# OCTOBOARDV_1_1.net
KiCad netlist of a schematic drawn in EAGLE
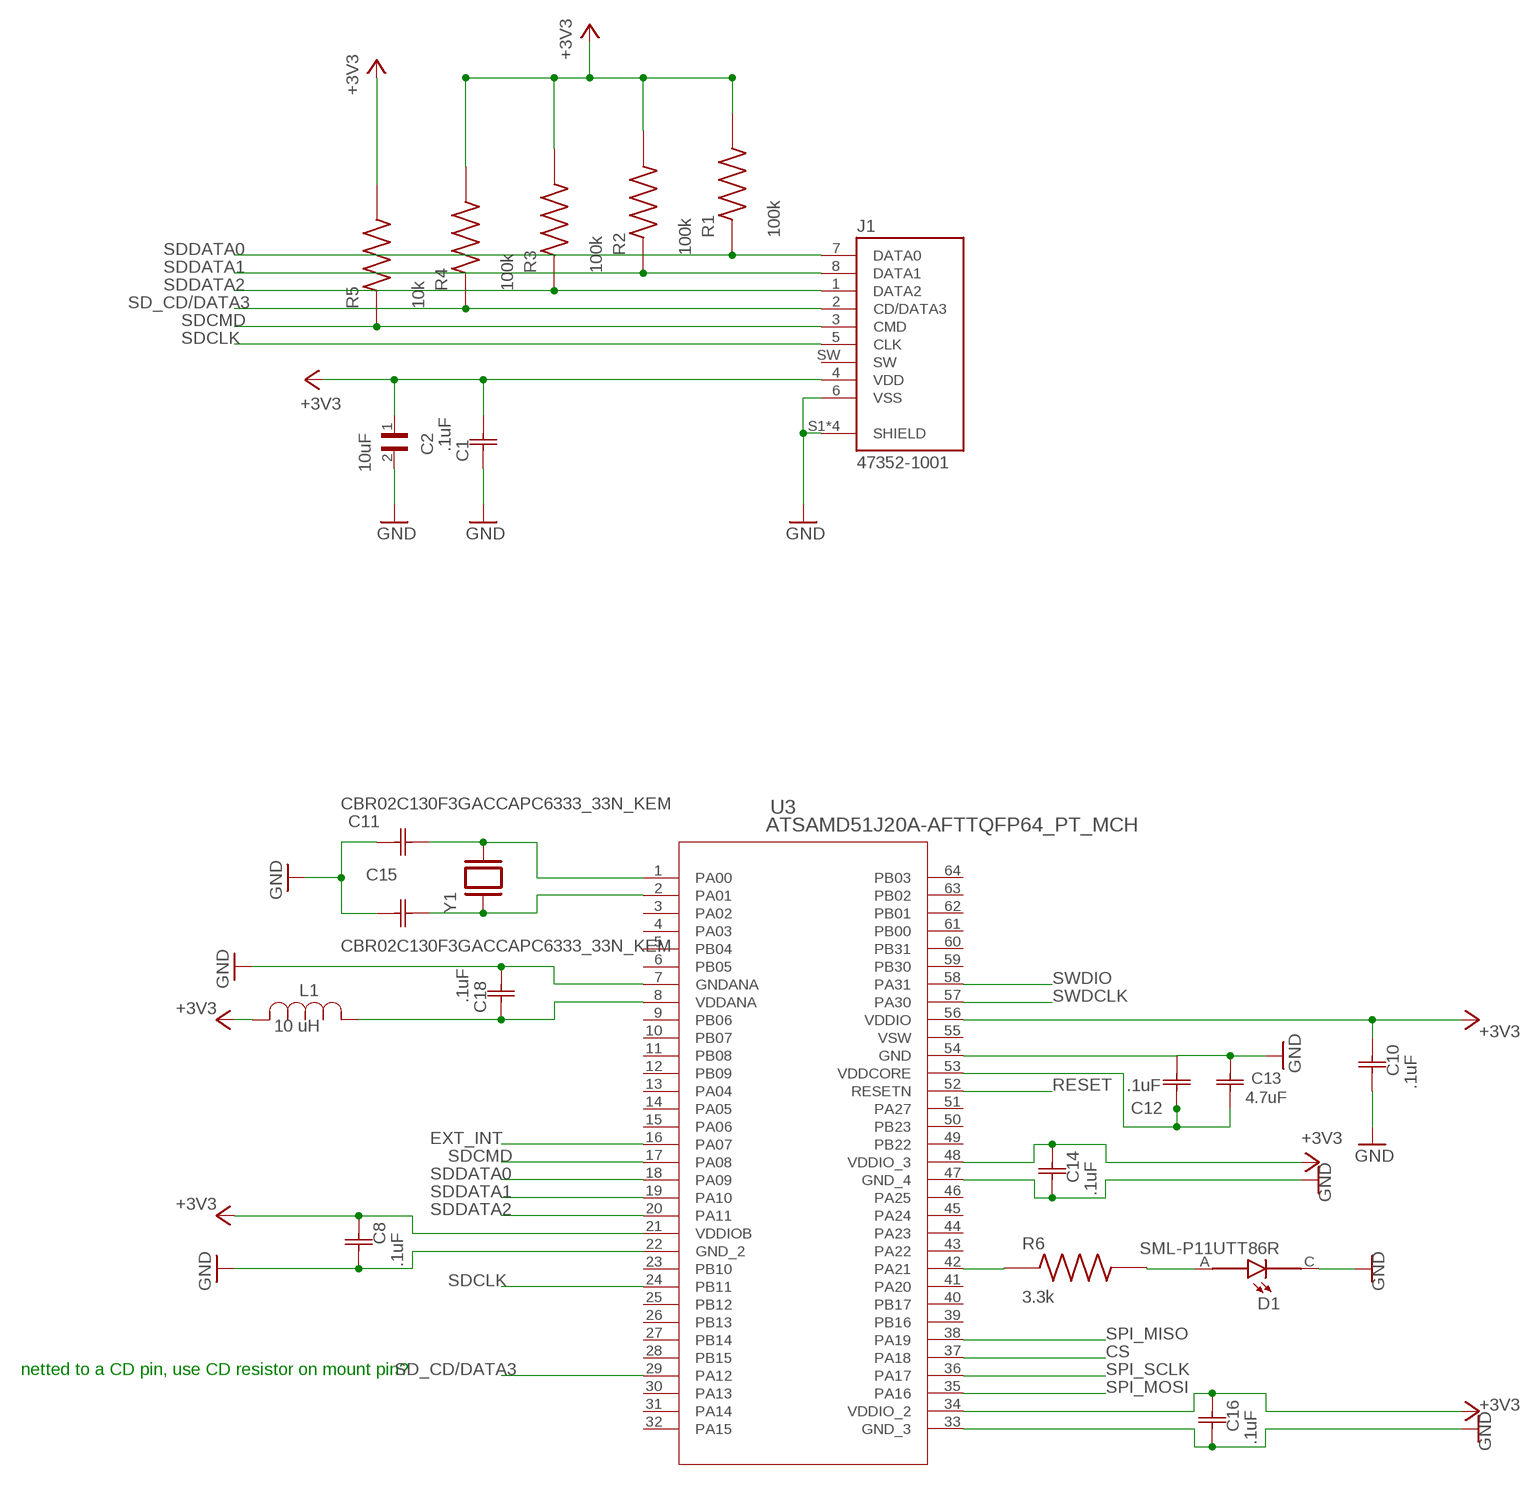
[diagram p0: schematic, sheet 1, part 1 of 2]
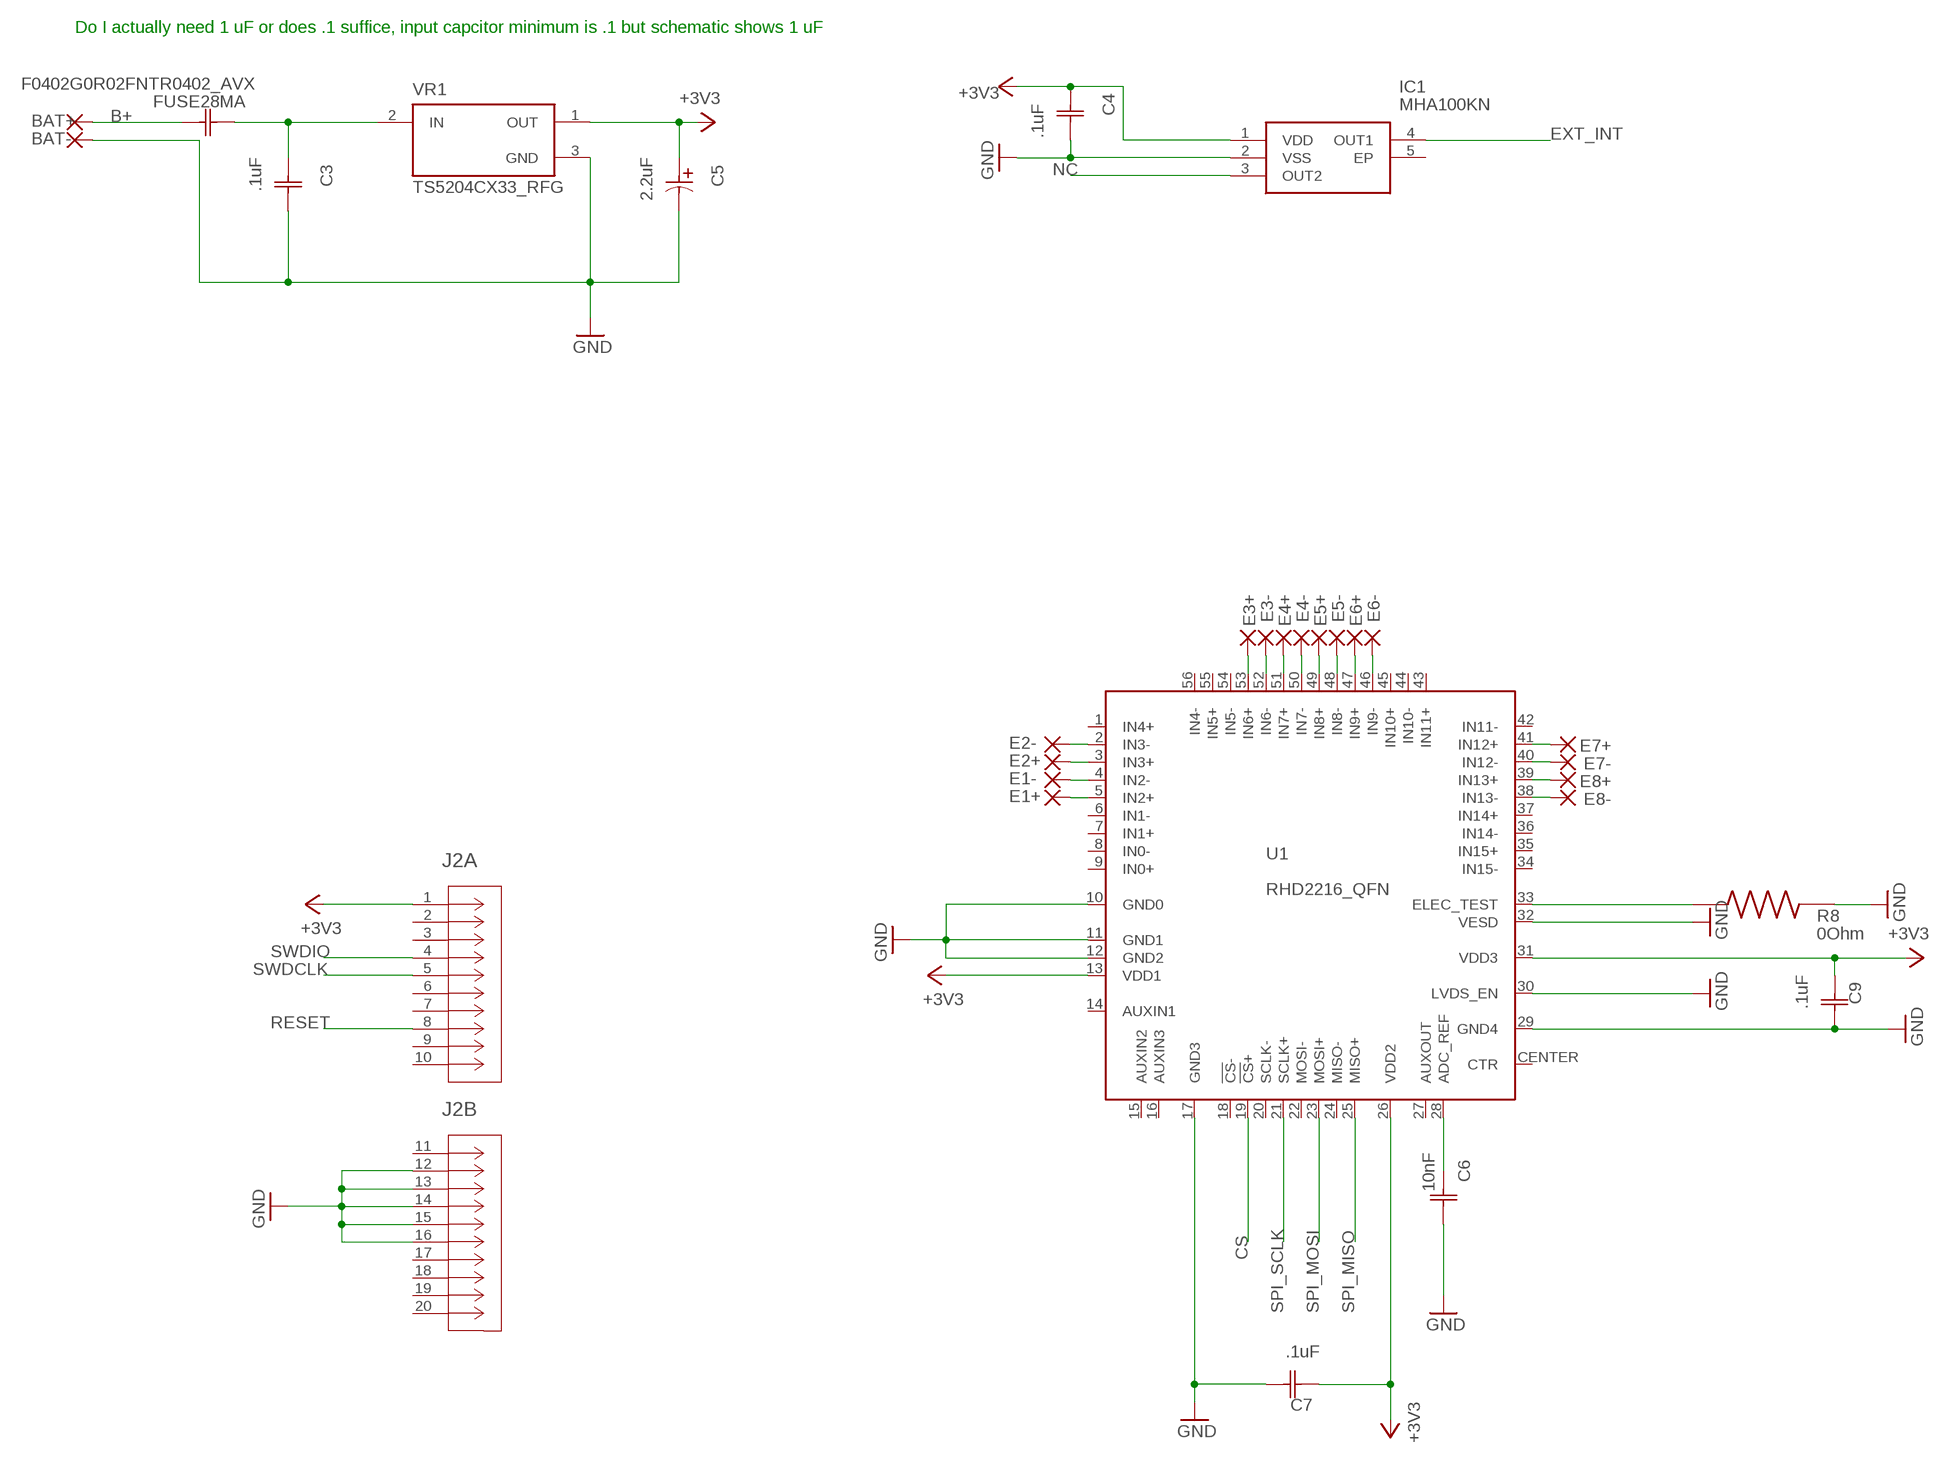
[diagram p1: schematic, sheet 1, part 2 of 2]

(export (version "E")
  (design (tool "Eeschema 10.0.6"))
  (components
    (comp (ref "BAT+")
      (value "1.36/.71LEAD")
      (footprint "eagle-import:1,6_0,9")
      (libsource (lib "eagle-import") (part "1.36/.71LEAD"))
    )
    (comp (ref "BAT-")
      (value "1.36/.71LEAD")
      (footprint "eagle-import:1,6_0,9")
      (libsource (lib "eagle-import") (part "1.36/.71LEAD"))
    )
    (comp (ref "C1")
      (value ".1uF")
      (footprint "eagle-import:CAP_0402_WAL")
      (fields
        (field (name "MANUFACTURER_PART_NUMBER") "0402B104K250CT")
        (field (name "COPYRIGHT") "Copyright (C) 2023 Ultra Librarian. All rights reserved.")
      )
      (libsource (lib "eagle-import") (part "0402B104K250CTCAP_0402_WAL"))
    )
    (comp (ref "C2")
      (value "10uF")
      (footprint "eagle-import:CAPC1005X70N")
      (fields (field (name "MF") "Murata Electronics") (field (name "MP") "GRM155R61A106ME11D"))
      (libsource (lib "eagle-import") (part "GRM155R61A106ME11D"))
    )
    (comp (ref "C3")
      (value ".1uF")
      (footprint "eagle-import:CAP_0402_WAL")
      (fields
        (field (name "MANUFACTURER_PART_NUMBER") "0402B104K250CT")
        (field (name "COPYRIGHT") "Copyright (C) 2023 Ultra Librarian. All rights reserved.")
      )
      (libsource (lib "eagle-import") (part "0402B104K250CTCAP_0402_WAL"))
    )
    (comp (ref "C4")
      (value ".1uF")
      (footprint "eagle-import:CAP_0402_WAL")
      (fields
        (field (name "MANUFACTURER_PART_NUMBER") "0402B104K250CT")
        (field (name "COPYRIGHT") "Copyright (C) 2023 Ultra Librarian. All rights reserved.")
      )
      (libsource (lib "eagle-import") (part "0402B104K250CTCAP_0402_WAL"))
    )
    (comp (ref "C5")
      (value "2.2uF")
      (footprint "eagle-import:CAPMP3.4X1.6_1.8N_KEM")
      (fields
        (field (name "MANUFACTURER_PART_NUMBER") "T491A225K016ATAUTO")
        (field (name "COPYRIGHT") "Copyright (C) 2023 Ultra Librarian. All rights reserved.")
      )
      (libsource (lib "eagle-import") (part "T491A225K016ATAUTOCAPMP3.4X1.6_1.8N_KEM"))
    )
    (comp (ref "C6")
      (value "10nF")
      (footprint "eagle-import:CAP_00J25AH_AVX")
      (fields
        (field (name "MANUFACTURER_PART_NUMBER") "CM02X5R103M16AH")
        (field (name "COPYRIGHT") "Copyright (C) 2023 Ultra Librarian. All rights reserved.")
      )
      (libsource (lib "eagle-import") (part "CM02X5R103M16AHCAP_00J25AH_AVX"))
    )
    (comp (ref "C7")
      (value ".1uF")
      (footprint "eagle-import:CAP_0402_WAL")
      (fields
        (field (name "MANUFACTURER_PART_NUMBER") "0402B104K250CT")
        (field (name "COPYRIGHT") "Copyright (C) 2023 Ultra Librarian. All rights reserved.")
      )
      (libsource (lib "eagle-import") (part "0402B104K250CTCAP_0402_WAL"))
    )
    (comp (ref "C8")
      (value ".1uF")
      (footprint "eagle-import:CAP_0402_WAL")
      (fields
        (field (name "MANUFACTURER_PART_NUMBER") "0402B104K250CT")
        (field (name "COPYRIGHT") "Copyright (C) 2023 Ultra Librarian. All rights reserved.")
      )
      (libsource (lib "eagle-import") (part "0402B104K250CTCAP_0402_WAL"))
    )
    (comp (ref "C9")
      (value ".1uF")
      (footprint "eagle-import:CAP_0402_WAL")
      (fields
        (field (name "MANUFACTURER_PART_NUMBER") "0402B104K250CT")
        (field (name "COPYRIGHT") "Copyright (C) 2023 Ultra Librarian. All rights reserved.")
      )
      (libsource (lib "eagle-import") (part "0402B104K250CTCAP_0402_WAL"))
    )
    (comp (ref "C10")
      (value ".1uF")
      (footprint "eagle-import:CAP_0402_WAL")
      (fields
        (field (name "MANUFACTURER_PART_NUMBER") "0402B104K250CT")
        (field (name "COPYRIGHT") "Copyright (C) 2023 Ultra Librarian. All rights reserved.")
      )
      (libsource (lib "eagle-import") (part "0402B104K250CTCAP_0402_WAL"))
    )
    (comp (ref "C11")
      (value "CBR02C130F3GACCAPC6333_33N_KEM")
      (footprint "eagle-import:CAPC6333_33N_KEM")
      (fields
        (field (name "MANUFACTURER_PART_NUMBER") "CBR02C130F3GAC")
        (field (name "COPYRIGHT") "Copyright (C) 2023 Ultra Librarian. All rights reserved.")
      )
      (libsource (lib "eagle-import") (part "CBR02C130F3GACCAPC6333_33N_KEM"))
    )
    (comp (ref "C12")
      (value ".1uF")
      (footprint "eagle-import:CAP_0402_WAL")
      (fields
        (field (name "MANUFACTURER_PART_NUMBER") "0402B104K250CT")
        (field (name "COPYRIGHT") "Copyright (C) 2023 Ultra Librarian. All rights reserved.")
      )
      (libsource (lib "eagle-import") (part "0402B104K250CTCAP_0402_WAL"))
    )
    (comp (ref "C13")
      (value "4.7uF")
      (footprint "eagle-import:CAP_CM03_F_KAV")
      (fields
        (field (name "MANUFACTURER_PART_NUMBER") "CM03X5R475M06AH055")
        (field (name "COPYRIGHT") "Copyright (C) 2023 Ultra Librarian. All rights reserved.")
      )
      (libsource (lib "eagle-import") (part "CM03X5R475M06AH055CAP_CM03_F_KAV"))
    )
    (comp (ref "C14")
      (value ".1uF")
      (footprint "eagle-import:CAP_0402_WAL")
      (fields
        (field (name "MANUFACTURER_PART_NUMBER") "0402B104K250CT")
        (field (name "COPYRIGHT") "Copyright (C) 2023 Ultra Librarian. All rights reserved.")
      )
      (libsource (lib "eagle-import") (part "0402B104K250CTCAP_0402_WAL"))
    )
    (comp (ref "C15")
      (value "CBR02C130F3GACCAPC6333_33N_KEM")
      (footprint "eagle-import:CAPC6333_33N_KEM")
      (fields
        (field (name "MANUFACTURER_PART_NUMBER") "CBR02C130F3GAC")
        (field (name "COPYRIGHT") "Copyright (C) 2023 Ultra Librarian. All rights reserved.")
      )
      (libsource (lib "eagle-import") (part "CBR02C130F3GACCAPC6333_33N_KEM"))
    )
    (comp (ref "C16")
      (value ".1uF")
      (footprint "eagle-import:CAP_0402_WAL")
      (fields
        (field (name "MANUFACTURER_PART_NUMBER") "0402B104K250CT")
        (field (name "COPYRIGHT") "Copyright (C) 2023 Ultra Librarian. All rights reserved.")
      )
      (libsource (lib "eagle-import") (part "0402B104K250CTCAP_0402_WAL"))
    )
    (comp (ref "C18")
      (value ".1uF")
      (footprint "eagle-import:CAP_0402_WAL")
      (fields
        (field (name "MANUFACTURER_PART_NUMBER") "0402B104K250CT")
        (field (name "COPYRIGHT") "Copyright (C) 2023 Ultra Librarian. All rights reserved.")
      )
      (libsource (lib "eagle-import") (part "0402B104K250CTCAP_0402_WAL"))
    )
    (comp (ref "D1")
      (value "SML-P11UTT86R")
      (footprint "eagle-import:LED_SML-P11UTT86R")
      (fields (field (name "MANUFACTURER") "ROHM Semiconductor"))
      (libsource (lib "eagle-import") (part "SML-P11UTT86R"))
    )
    (comp (ref "E1+")
      (value "1.36/.71LEAD")
      (footprint "eagle-import:1,6_0,9")
      (libsource (lib "eagle-import") (part "1.36/.71LEAD"))
    )
    (comp (ref "E1-")
      (value "1.36/.71LEAD")
      (footprint "eagle-import:1,6_0,9")
      (libsource (lib "eagle-import") (part "1.36/.71LEAD"))
    )
    (comp (ref "E2+")
      (value "1.36/.71LEAD")
      (footprint "eagle-import:1,6_0,9")
      (libsource (lib "eagle-import") (part "1.36/.71LEAD"))
    )
    (comp (ref "E2-")
      (value "1.36/.71LEAD")
      (footprint "eagle-import:1,6_0,9")
      (libsource (lib "eagle-import") (part "1.36/.71LEAD"))
    )
    (comp (ref "E3+")
      (value "1.36/.71LEAD")
      (footprint "eagle-import:1,6_0,9")
      (libsource (lib "eagle-import") (part "1.36/.71LEAD"))
    )
    (comp (ref "E3-")
      (value "1.36/.71LEAD")
      (footprint "eagle-import:1,6_0,9")
      (libsource (lib "eagle-import") (part "1.36/.71LEAD"))
    )
    (comp (ref "E4+")
      (value "1.36/.71LEAD")
      (footprint "eagle-import:1,6_0,9")
      (libsource (lib "eagle-import") (part "1.36/.71LEAD"))
    )
    (comp (ref "E4-")
      (value "1.36/.71LEAD")
      (footprint "eagle-import:1,6_0,9")
      (libsource (lib "eagle-import") (part "1.36/.71LEAD"))
    )
    (comp (ref "E5+")
      (value "1.36/.71LEAD")
      (footprint "eagle-import:1,6_0,9")
      (libsource (lib "eagle-import") (part "1.36/.71LEAD"))
    )
    (comp (ref "E5-")
      (value "1.36/.71LEAD")
      (footprint "eagle-import:1,6_0,9")
      (libsource (lib "eagle-import") (part "1.36/.71LEAD"))
    )
    (comp (ref "E6+")
      (value "1.36/.71LEAD")
      (footprint "eagle-import:1,6_0,9")
      (libsource (lib "eagle-import") (part "1.36/.71LEAD"))
    )
    (comp (ref "E6-")
      (value "1.36/.71LEAD")
      (footprint "eagle-import:1,6_0,9")
      (libsource (lib "eagle-import") (part "1.36/.71LEAD"))
    )
    (comp (ref "E7+")
      (value "1.36/.71LEAD")
      (footprint "eagle-import:1,6_0,9")
      (libsource (lib "eagle-import") (part "1.36/.71LEAD"))
    )
    (comp (ref "E7-")
      (value "1.36/.71LEAD")
      (footprint "eagle-import:1,6_0,9")
      (libsource (lib "eagle-import") (part "1.36/.71LEAD"))
    )
    (comp (ref "E8+")
      (value "1.36/.71LEAD")
      (footprint "eagle-import:1,6_0,9")
      (libsource (lib "eagle-import") (part "1.36/.71LEAD"))
    )
    (comp (ref "E8-")
      (value "1.36/.71LEAD")
      (footprint "eagle-import:1,6_0,9")
      (libsource (lib "eagle-import") (part "1.36/.71LEAD"))
    )
    (comp (ref "FUSE28MA")
      (value "F0402G0R02FNTR0402_AVX")
      (footprint "eagle-import:0402_AVX")
      (fields
        (field (name "MANUFACTURER_PART_NUMBER") "F0402G0R20FNTR")
        (field (name "COPYRIGHT") "Copyright (C) 2023 Ultra Librarian. All rights reserved.")
      )
      (libsource (lib "eagle-import") (part "F0402G0R20FNTR0402_AVX"))
    )
    (comp (ref "IC1")
      (value "MHA100KN")
      (footprint "eagle-import:MHA100KN")
      (fields (field (name "MOUSER_PART_NUMBER") "438-MHA100KN"))
      (libsource (lib "eagle-import") (part "MHA100KN"))
    )
    (comp (ref "J1")
      (value "47352-1001")
      (footprint "eagle-import:MOLEX_47352-1001")
      (fields (field (name "DIGI-KEY_PART_NUMBER") "WM3290CT-ND") (field (name "MF") "Molex"))
      (libsource (lib "eagle-import") (part "47352-1001"))
    )
    (comp (ref "J2")
      (value "PRPC040DAAN-RCCONN80_PRP-040_4000X197_SUL")
      (footprint "eagle-import:CONN80_PRP-040_4000X197_SUL")
      (fields
        (field (name "MANUFACTURER_PART_NUMBER") "PRPC040DAAN-RC")
        (field (name "COPYRIGHT") "Copyright (C) 2023 Ultra Librarian. All rights reserved.")
      )
      (libsource (lib "eagle-import") (part "PRPC040DAAN-RCCONN80_PRP-040_4000X197_SUL"))
    )
    (comp (ref "L1")
      (value "10 uH")
      (footprint "eagle-import:IND_SDEB12101T_CYN")
      (fields
        (field (name "MANUFACTURER_PART_NUMBER") "SDEB12101T-100MSD")
        (field (name "COPYRIGHT") "Copyright (C) 2023 Ultra Librarian. All rights reserved.")
      )
      (libsource (lib "eagle-import") (part "SDEB12101T-100MSDIND_SDEB12101T_CYN"))
    )
    (comp (ref "R1")
      (value "100k")
      (footprint "eagle-import:RES_ERJ1GNJ104C")
      (fields (field (name "MF") "Panasonic") (field (name "MP") "ERJ-1GNJ104C"))
      (libsource (lib "eagle-import") (part "ERJ1GNJ104C"))
    )
    (comp (ref "R2")
      (value "100k")
      (footprint "eagle-import:RES_ERJ1GNJ104C")
      (fields (field (name "MF") "Panasonic") (field (name "MP") "ERJ-1GNJ104C"))
      (libsource (lib "eagle-import") (part "ERJ1GNJ104C"))
    )
    (comp (ref "R3")
      (value "100k")
      (footprint "eagle-import:RES_ERJ1GNJ104C")
      (fields (field (name "MF") "Panasonic") (field (name "MP") "ERJ-1GNJ104C"))
      (libsource (lib "eagle-import") (part "ERJ1GNJ104C"))
    )
    (comp (ref "R4")
      (value "100k")
      (footprint "eagle-import:RES_ERJ1GNJ104C")
      (fields (field (name "MF") "Panasonic") (field (name "MP") "ERJ-1GNJ104C"))
      (libsource (lib "eagle-import") (part "ERJ1GNJ104C"))
    )
    (comp (ref "R5")
      (value "10k")
      (footprint "eagle-import:RES_ERJ-1RHD1002C")
      (fields (field (name "MF") "Panasonic Electronic") (field (name "MP") "ERJ-1RHD1002C"))
      (libsource (lib "eagle-import") (part "ERJ-1RHD1002C"))
    )
    (comp (ref "R6")
      (value "3.3k")
      (footprint "eagle-import:RESC0603X26N")
      (libsource (lib "eagle-import") (part "ERJ-1GNF3301C"))
    )
    (comp (ref "R8")
      (value "0Ohm")
      (footprint "eagle-import:RESC0603X26N")
      (fields (field (name "MF") "Stackpole Electronics Inc") (field (name "MP") "RMCF0201ZT0R00"))
      (libsource (lib "eagle-import") (part "RMCF0201ZT0R00"))
    )
    (comp (ref "U1")
      (value "RHD2216_QFN")
      (footprint "eagle-import:QFN56_8_X_8_LARGE")
      (libsource (lib "eagle-import") (part "RHD2216_QFN"))
    )
    (comp (ref "U3")
      (value "ATSAMD51J20A-AFTTQFP64_PT_MCH")
      (footprint "eagle-import:TQFP64_PT_MCH")
      (fields
        (field (name "MANUFACTURER_PART_NUMBER") "ATSAMD51J20A-AFT")
        (field (name "COPYRIGHT") "Copyright (C) 2023 Ultra Librarian. All rights reserved.")
      )
      (libsource (lib "eagle-import") (part "ATSAMD51J20A-AFTTQFP64_PT_MCH"))
    )
    (comp (ref "VR1")
      (value "TS5204CX33_RFG")
      (footprint "eagle-import:SOT95P280X110-3N")
      (fields (field (name "MF") "Taiwan Semiconductor Corporation") (field (name "MP") "TS5204CX33 RFG"))
      (libsource (lib "eagle-import") (part "TS5204CX33_RFG"))
    )
    (comp (ref "Y1")
      (value "CM9V-T1A-32.768KHZ-9PF-20PPM-TA-QC")
      (footprint "eagle-import:XTAL_CM9V-T1A-32.768KHZ-9PF-20PPM-TA-QC")
      (fields (field (name "MF") "Micro Crystal AG"))
      (libsource (lib "eagle-import") (part "CM9V-T1A-32.768KHZ-9PF-20PPM-TA-QC"))
    )
  )
  (nets
    (net (code "1") (name "+3V3") (class "Default")
      (node (ref "C1") (pin "2") (pinfunction "2_2") (pintype "passive"))
      (node (ref "C10") (pin "1") (pinfunction "1_1") (pintype "passive"))
      (node (ref "C14") (pin "1") (pinfunction "1_1") (pintype "passive"))
      (node (ref "C16") (pin "1") (pinfunction "1_1") (pintype "passive"))
      (node (ref "C2") (pin "1") (pinfunction "1_1") (pintype "passive"))
      (node (ref "C4") (pin "1") (pinfunction "1_1") (pintype "passive"))
      (node (ref "C5") (pin "1") (pinfunction "1_1") (pintype "passive"))
      (node (ref "C7") (pin "1") (pinfunction "1_1") (pintype "passive"))
      (node (ref "C8") (pin "1") (pinfunction "1_1") (pintype "passive"))
      (node (ref "C9") (pin "1") (pinfunction "1_1") (pintype "passive"))
      (node (ref "IC1") (pin "1") (pinfunction "VDD_1") (pintype "bidirectional"))
      (node (ref "J1") (pin "4") (pinfunction "VDD_4") (pintype "passive"))
      (node (ref "J2") (pin "1") (pinfunction "1_1") (pintype "passive"))
      (node (ref "L1") (pin "2") (pinfunction "2_2") (pintype "passive"))
      (node (ref "R1") (pin "2") (pinfunction "2_2") (pintype "passive"))
      (node (ref "R2") (pin "2") (pinfunction "2_2") (pintype "passive"))
      (node (ref "R3") (pin "2") (pinfunction "2_2") (pintype "passive"))
      (node (ref "R4") (pin "2") (pinfunction "2_2") (pintype "passive"))
      (node (ref "R5") (pin "2") (pinfunction "2_2") (pintype "passive"))
      (node (ref "U1") (pin "13") (pinfunction "VDD1_13") (pintype "power_in"))
      (node (ref "U1") (pin "26") (pinfunction "VDD2_26") (pintype "power_in"))
      (node (ref "U1") (pin "31") (pinfunction "VDD3_31") (pintype "power_in"))
      (node (ref "U3") (pin "21") (pinfunction "VDDIOB_21") (pintype "power_in"))
      (node (ref "U3") (pin "34") (pinfunction "VDDIO_2_34") (pintype "power_in"))
      (node (ref "U3") (pin "48") (pinfunction "VDDIO_3_48") (pintype "power_in"))
      (node (ref "U3") (pin "56") (pinfunction "VDDIO_56") (pintype "power_in"))
      (node (ref "VR1") (pin "1") (pinfunction "OUT_1") (pintype "output"))
    )
    (net (code "2") (name "/B+") (class "Default")
      (node (ref "BAT+") (pin "1") (pinfunction "P_1") (pintype "passive"))
      (node (ref "FUSE28MA") (pin "1") (pinfunction "11_1") (pintype "passive"))
    )
    (net (code "3") (name "/CS") (class "Default")
      (node (ref "U1") (pin "19") (pinfunction "~{CS}+_19") (pintype "input"))
      (node (ref "U3") (pin "37") (pinfunction "PA18_37") (pintype "bidirectional"))
    )
    (net (code "4") (name "/CTR") (class "Default")
      (node (ref "U1") (pin "CENTER") (pinfunction "CTR_CENTER") (pintype "power_in"))
    )
    (net (code "5") (name "/EXT_INT") (class "Default")
      (node (ref "IC1") (pin "4") (pinfunction "OUT1_4") (pintype "bidirectional"))
      (node (ref "U3") (pin "16") (pinfunction "PA07_16") (pintype "bidirectional"))
    )
    (net (code "6") (name "/NC") (class "Default")
      (node (ref "IC1") (pin "3") (pinfunction "OUT2_3") (pintype "bidirectional"))
    )
    (net (code "7") (name "/RESET") (class "Default")
      (node (ref "J2") (pin "8") (pinfunction "8_8") (pintype "passive"))
      (node (ref "U3") (pin "52") (pinfunction "RESETN_52") (pintype "input"))
    )
    (net (code "8") (name "/SDCLK") (class "Default")
      (node (ref "J1") (pin "5") (pinfunction "CLK_5") (pintype "passive"))
      (node (ref "U3") (pin "24") (pinfunction "PB11_24") (pintype "bidirectional"))
    )
    (net (code "9") (name "/SDCMD") (class "Default")
      (node (ref "J1") (pin "3") (pinfunction "CMD_3") (pintype "passive"))
      (node (ref "R5") (pin "1") (pinfunction "1_1") (pintype "passive"))
      (node (ref "U3") (pin "17") (pinfunction "PA08_17") (pintype "bidirectional"))
    )
    (net (code "10") (name "/SDDATA0") (class "Default")
      (node (ref "J1") (pin "7") (pinfunction "DATA0_7") (pintype "passive"))
      (node (ref "R1") (pin "1") (pinfunction "1_1") (pintype "passive"))
      (node (ref "U3") (pin "18") (pinfunction "PA09_18") (pintype "bidirectional"))
    )
    (net (code "11") (name "/SDDATA1") (class "Default")
      (node (ref "J1") (pin "8") (pinfunction "DATA1_8") (pintype "passive"))
      (node (ref "R2") (pin "1") (pinfunction "1_1") (pintype "passive"))
      (node (ref "U3") (pin "19") (pinfunction "PA10_19") (pintype "bidirectional"))
    )
    (net (code "12") (name "/SDDATA2") (class "Default")
      (node (ref "J1") (pin "1") (pinfunction "DATA2_1") (pintype "passive"))
      (node (ref "R3") (pin "1") (pinfunction "1_1") (pintype "passive"))
      (node (ref "U3") (pin "20") (pinfunction "PA11_20") (pintype "bidirectional"))
    )
    (net (code "13") (name "/SD_CD{slash}DATA3") (class "Default")
      (node (ref "J1") (pin "2") (pinfunction "CD/DATA3_2") (pintype "passive"))
      (node (ref "R4") (pin "1") (pinfunction "1_1") (pintype "passive"))
      (node (ref "U3") (pin "29") (pinfunction "PA12_29") (pintype "bidirectional"))
    )
    (net (code "14") (name "/SPI_MISO") (class "Default")
      (node (ref "U1") (pin "25") (pinfunction "MISO+_25") (pintype "output"))
      (node (ref "U3") (pin "38") (pinfunction "PA19_38") (pintype "bidirectional"))
    )
    (net (code "15") (name "/SPI_MOSI") (class "Default")
      (node (ref "U1") (pin "23") (pinfunction "MOSI+_23") (pintype "input"))
      (node (ref "U3") (pin "35") (pinfunction "PA16_35") (pintype "bidirectional"))
    )
    (net (code "16") (name "/SPI_SCLK") (class "Default")
      (node (ref "U1") (pin "21") (pinfunction "SCLK+_21") (pintype "input"))
      (node (ref "U3") (pin "36") (pinfunction "PA17_36") (pintype "bidirectional"))
    )
    (net (code "17") (name "/SWDCLK") (class "Default")
      (node (ref "J2") (pin "5") (pinfunction "5_5") (pintype "passive"))
      (node (ref "U3") (pin "57") (pinfunction "PA30_57") (pintype "bidirectional"))
    )
    (net (code "18") (name "/SWDIO") (class "Default")
      (node (ref "J2") (pin "4") (pinfunction "4_4") (pintype "passive"))
      (node (ref "U3") (pin "58") (pinfunction "PA31_58") (pintype "bidirectional"))
    )
    (net (code "19") (name "/VSW") (class "Default")
      (node (ref "U3") (pin "55") (pinfunction "VSW_55") (pintype "power_in"))
    )
    (net (code "20") (name "GND") (class "Default")
      (node (ref "BAT-") (pin "1") (pinfunction "P_1") (pintype "passive"))
      (node (ref "C1") (pin "1") (pinfunction "1_1") (pintype "passive"))
      (node (ref "C10") (pin "2") (pinfunction "2_2") (pintype "passive"))
      (node (ref "C11") (pin "1") (pinfunction "1_1") (pintype "passive"))
      (node (ref "C12") (pin "2") (pinfunction "2_2") (pintype "passive"))
      (node (ref "C13") (pin "2") (pinfunction "2_2") (pintype "passive"))
      (node (ref "C14") (pin "2") (pinfunction "2_2") (pintype "passive"))
      (node (ref "C15") (pin "1") (pinfunction "1_1") (pintype "passive"))
      (node (ref "C16") (pin "2") (pinfunction "2_2") (pintype "passive"))
      (node (ref "C18") (pin "2") (pinfunction "2_2") (pintype "passive"))
      (node (ref "C2") (pin "2") (pinfunction "2_2") (pintype "passive"))
      (node (ref "C3") (pin "2") (pinfunction "2_2") (pintype "passive"))
      (node (ref "C4") (pin "2") (pinfunction "2_2") (pintype "passive"))
      (node (ref "C5") (pin "2") (pinfunction "2_2") (pintype "passive"))
      (node (ref "C6") (pin "2") (pinfunction "2_2") (pintype "passive"))
      (node (ref "C7") (pin "2") (pinfunction "2_2") (pintype "passive"))
      (node (ref "C8") (pin "2") (pinfunction "2_2") (pintype "passive"))
      (node (ref "C9") (pin "2") (pinfunction "2_2") (pintype "passive"))
      (node (ref "D1") (pin "C") (pinfunction "C_C") (pintype "passive"))
      (node (ref "IC1") (pin "2") (pinfunction "VSS_2") (pintype "bidirectional"))
      (node (ref "J1") (pin "6") (pinfunction "VSS_6") (pintype "passive"))
      (node (ref "J1") (pin "S1") (pinfunction "SHIELD_S1") (pintype "passive"))
      (node (ref "J1") (pin "S2") (pinfunction "SHIELD_S2") (pintype "passive"))
      (node (ref "J1") (pin "S3") (pinfunction "SHIELD_S3") (pintype "passive"))
      (node (ref "J1") (pin "S4") (pinfunction "SHIELD_S4") (pintype "passive"))
      (node (ref "J2") (pin "12") (pinfunction "42_12") (pintype "passive"))
      (node (ref "J2") (pin "13") (pinfunction "43_13") (pintype "passive"))
      (node (ref "J2") (pin "14") (pinfunction "44_14") (pintype "passive"))
      (node (ref "J2") (pin "15") (pinfunction "45_15") (pintype "passive"))
      (node (ref "J2") (pin "16") (pinfunction "46_16") (pintype "passive"))
      (node (ref "R8") (pin "2") (pinfunction "2_2") (pintype "passive"))
      (node (ref "U1") (pin "10") (pinfunction "GND0_10") (pintype "input"))
      (node (ref "U1") (pin "11") (pinfunction "GND1_11") (pintype "power_in"))
      (node (ref "U1") (pin "12") (pinfunction "GND2_12") (pintype "power_in"))
      (node (ref "U1") (pin "17") (pinfunction "GND3_17") (pintype "power_in"))
      (node (ref "U1") (pin "29") (pinfunction "GND4_29") (pintype "power_in"))
      (node (ref "U1") (pin "30") (pinfunction "LVDS_EN_30") (pintype "input"))
      (node (ref "U1") (pin "32") (pinfunction "VESD_32") (pintype "power_in"))
      (node (ref "U3") (pin "22") (pinfunction "GND_2_22") (pintype "passive"))
      (node (ref "U3") (pin "33") (pinfunction "GND_3_33") (pintype "passive"))
      (node (ref "U3") (pin "47") (pinfunction "GND_4_47") (pintype "passive"))
      (node (ref "U3") (pin "54") (pinfunction "GND_54") (pintype "passive"))
      (node (ref "U3") (pin "7") (pinfunction "GNDANA_7") (pintype "passive"))
      (node (ref "VR1") (pin "3") (pinfunction "GND_3") (pintype "power_in"))
    )
    (net (code "21") (name "Net-(D1-PadA)") (class "Default")
      (node (ref "D1") (pin "A") (pinfunction "A_A") (pintype "passive"))
      (node (ref "R6") (pin "2") (pinfunction "2_2") (pintype "passive"))
    )
    (net (code "22") (name "Net-(E1+-P)") (class "Default")
      (node (ref "E1+") (pin "1") (pinfunction "P_1") (pintype "passive"))
      (node (ref "U1") (pin "5") (pinfunction "IN2+_5") (pintype "input"))
    )
    (net (code "23") (name "Net-(E1--P)") (class "Default")
      (node (ref "E1-") (pin "1") (pinfunction "P_1") (pintype "passive"))
      (node (ref "U1") (pin "4") (pinfunction "IN2-_4") (pintype "input"))
    )
    (net (code "24") (name "Net-(E2+-P)") (class "Default")
      (node (ref "E2+") (pin "1") (pinfunction "P_1") (pintype "passive"))
      (node (ref "U1") (pin "3") (pinfunction "IN3+_3") (pintype "input"))
    )
    (net (code "25") (name "Net-(E2--P)") (class "Default")
      (node (ref "E2-") (pin "1") (pinfunction "P_1") (pintype "passive"))
      (node (ref "U1") (pin "2") (pinfunction "IN3-_2") (pintype "input"))
    )
    (net (code "26") (name "Net-(E3+-P)") (class "Default")
      (node (ref "E3+") (pin "1") (pinfunction "P_1") (pintype "passive"))
      (node (ref "U1") (pin "53") (pinfunction "IN6+_53") (pintype "input"))
    )
    (net (code "27") (name "Net-(E3--P)") (class "Default")
      (node (ref "E3-") (pin "1") (pinfunction "P_1") (pintype "passive"))
      (node (ref "U1") (pin "52") (pinfunction "IN6-_52") (pintype "input"))
    )
    (net (code "28") (name "Net-(E4+-P)") (class "Default")
      (node (ref "E4+") (pin "1") (pinfunction "P_1") (pintype "passive"))
      (node (ref "U1") (pin "51") (pinfunction "IN7+_51") (pintype "input"))
    )
    (net (code "29") (name "Net-(E4--P)") (class "Default")
      (node (ref "E4-") (pin "1") (pinfunction "P_1") (pintype "passive"))
      (node (ref "U1") (pin "50") (pinfunction "IN7-_50") (pintype "input"))
    )
    (net (code "30") (name "Net-(E5+-P)") (class "Default")
      (node (ref "E5+") (pin "1") (pinfunction "P_1") (pintype "passive"))
      (node (ref "U1") (pin "49") (pinfunction "IN8+_49") (pintype "input"))
    )
    (net (code "31") (name "Net-(E5--P)") (class "Default")
      (node (ref "E5-") (pin "1") (pinfunction "P_1") (pintype "passive"))
      (node (ref "U1") (pin "48") (pinfunction "IN8-_48") (pintype "input"))
    )
    (net (code "32") (name "Net-(E6+-P)") (class "Default")
      (node (ref "E6+") (pin "1") (pinfunction "P_1") (pintype "passive"))
      (node (ref "U1") (pin "47") (pinfunction "IN9+_47") (pintype "input"))
    )
    (net (code "33") (name "Net-(E6--P)") (class "Default")
      (node (ref "E6-") (pin "1") (pinfunction "P_1") (pintype "passive"))
      (node (ref "U1") (pin "46") (pinfunction "IN9-_46") (pintype "input"))
    )
    (net (code "34") (name "Net-(E7+-P)") (class "Default")
      (node (ref "E7+") (pin "1") (pinfunction "P_1") (pintype "passive"))
      (node (ref "U1") (pin "41") (pinfunction "IN12+_41") (pintype "input"))
    )
    (net (code "35") (name "Net-(E7--P)") (class "Default")
      (node (ref "E7-") (pin "1") (pinfunction "P_1") (pintype "passive"))
      (node (ref "U1") (pin "40") (pinfunction "IN12-_40") (pintype "input"))
    )
    (net (code "36") (name "Net-(E8+-P)") (class "Default")
      (node (ref "E8+") (pin "1") (pinfunction "P_1") (pintype "passive"))
      (node (ref "U1") (pin "39") (pinfunction "IN13+_39") (pintype "input"))
    )
    (net (code "37") (name "Net-(E8--P)") (class "Default")
      (node (ref "E8-") (pin "1") (pinfunction "P_1") (pintype "passive"))
      (node (ref "U1") (pin "38") (pinfunction "IN13-_38") (pintype "input"))
    )
    (net (code "38") (name "Net-(FUSE28MA-12)") (class "Default")
      (node (ref "C3") (pin "1") (pinfunction "1_1") (pintype "passive"))
      (node (ref "FUSE28MA") (pin "2") (pinfunction "12_2") (pintype "passive"))
      (node (ref "VR1") (pin "2") (pinfunction "IN_2") (pintype "input"))
    )
    (net (code "39") (name "Net-(U1-ADC_REF)") (class "Default")
      (node (ref "C6") (pin "1") (pinfunction "1_1") (pintype "passive"))
      (node (ref "U1") (pin "28") (pinfunction "ADC_REF_28") (pintype "passive"))
    )
    (net (code "40") (name "Net-(U1-ELEC_TEST)") (class "Default")
      (node (ref "R8") (pin "1") (pinfunction "1_1") (pintype "passive"))
      (node (ref "U1") (pin "33") (pinfunction "ELEC_TEST_33") (pintype "input"))
    )
    (net (code "41") (name "Net-(U3-PA00)") (class "Default")
      (node (ref "C11") (pin "2") (pinfunction "2_2") (pintype "passive"))
      (node (ref "U3") (pin "1") (pinfunction "PA00_1") (pintype "bidirectional"))
      (node (ref "Y1") (pin "2") (pinfunction "2_2") (pintype "passive"))
    )
    (net (code "42") (name "Net-(U3-PA01)") (class "Default")
      (node (ref "C15") (pin "2") (pinfunction "2_2") (pintype "passive"))
      (node (ref "U3") (pin "2") (pinfunction "PA01_2") (pintype "bidirectional"))
      (node (ref "Y1") (pin "1") (pinfunction "1_1") (pintype "passive"))
    )
    (net (code "43") (name "Net-(U3-PA21)") (class "Default")
      (node (ref "R6") (pin "1") (pinfunction "1_1") (pintype "passive"))
      (node (ref "U3") (pin "42") (pinfunction "PA21_42") (pintype "bidirectional"))
    )
    (net (code "44") (name "Net-(U3-VDDANA)") (class "Default")
      (node (ref "C18") (pin "1") (pinfunction "1_1") (pintype "passive"))
      (node (ref "L1") (pin "1") (pinfunction "1_1") (pintype "passive"))
      (node (ref "U3") (pin "8") (pinfunction "VDDANA_8") (pintype "power_in"))
    )
    (net (code "45") (name "Net-(U3-VDDCORE)") (class "Default")
      (node (ref "C12") (pin "1") (pinfunction "1_1") (pintype "passive"))
      (node (ref "C13") (pin "1") (pinfunction "1_1") (pintype "passive"))
      (node (ref "U3") (pin "53") (pinfunction "VDDCORE_53") (pintype "power_in"))
    )
    (net (code "46") (name "unconnected-(IC1-EP-Pad5)") (class "Default")
      (node (ref "IC1") (pin "5") (pinfunction "EP_5") (pintype "bidirectional"))
    )
    (net (code "47") (name "unconnected-(J1-PadSW)") (class "Default")
      (node (ref "J1") (pin "SW") (pinfunction "SW_SW") (pintype "passive"))
    )
    (net (code "48") (name "unconnected-(J2-Pad2)") (class "Default")
      (node (ref "J2") (pin "2") (pinfunction "2_2") (pintype "passive"))
    )
    (net (code "49") (name "unconnected-(J2-Pad3)") (class "Default")
      (node (ref "J2") (pin "3") (pinfunction "3_3") (pintype "passive"))
    )
    (net (code "50") (name "unconnected-(J2-Pad6)") (class "Default")
      (node (ref "J2") (pin "6") (pinfunction "6_6") (pintype "passive"))
    )
    (net (code "51") (name "unconnected-(J2-Pad7)") (class "Default")
      (node (ref "J2") (pin "7") (pinfunction "7_7") (pintype "passive"))
    )
    (net (code "52") (name "unconnected-(J2-Pad9)") (class "Default")
      (node (ref "J2") (pin "9") (pinfunction "9_9") (pintype "passive"))
    )
    (net (code "53") (name "unconnected-(J2-Pad10)") (class "Default")
      (node (ref "J2") (pin "10") (pinfunction "10_10") (pintype "passive"))
    )
    (net (code "54") (name "unconnected-(J2B-41-Pad11)") (class "Default")
      (node (ref "J2") (pin "11") (pinfunction "41_11") (pintype "passive"))
    )
    (net (code "55") (name "unconnected-(J2B-47-Pad17)") (class "Default")
      (node (ref "J2") (pin "17") (pinfunction "47_17") (pintype "passive"))
    )
    (net (code "56") (name "unconnected-(J2B-48-Pad18)") (class "Default")
      (node (ref "J2") (pin "18") (pinfunction "48_18") (pintype "passive"))
    )
    (net (code "57") (name "unconnected-(J2B-49-Pad19)") (class "Default")
      (node (ref "J2") (pin "19") (pinfunction "49_19") (pintype "passive"))
    )
    (net (code "58") (name "unconnected-(J2B-50-Pad20)") (class "Default")
      (node (ref "J2") (pin "20") (pinfunction "50_20") (pintype "passive"))
    )
    (net (code "59") (name "unconnected-(U1-AUXIN1-Pad14)") (class "Default")
      (node (ref "U1") (pin "14") (pinfunction "AUXIN1_14") (pintype "input"))
    )
    (net (code "60") (name "unconnected-(U1-AUXIN2-Pad15)") (class "Default")
      (node (ref "U1") (pin "15") (pinfunction "AUXIN2_15") (pintype "input"))
    )
    (net (code "61") (name "unconnected-(U1-AUXIN3-Pad16)") (class "Default")
      (node (ref "U1") (pin "16") (pinfunction "AUXIN3_16") (pintype "input"))
    )
    (net (code "62") (name "unconnected-(U1-AUXOUT-Pad27)") (class "Default")
      (node (ref "U1") (pin "27") (pinfunction "AUXOUT_27") (pintype "tri_state"))
    )
    (net (code "63") (name "unconnected-(U1-IN0+-Pad9)") (class "Default")
      (node (ref "U1") (pin "9") (pinfunction "IN0+_9") (pintype "input"))
    )
    (net (code "64") (name "unconnected-(U1-IN0--Pad8)") (class "Default")
      (node (ref "U1") (pin "8") (pinfunction "IN0-_8") (pintype "input"))
    )
    (net (code "65") (name "unconnected-(U1-IN1+-Pad7)") (class "Default")
      (node (ref "U1") (pin "7") (pinfunction "IN1+_7") (pintype "input"))
    )
    (net (code "66") (name "unconnected-(U1-IN1--Pad6)") (class "Default")
      (node (ref "U1") (pin "6") (pinfunction "IN1-_6") (pintype "input"))
    )
    (net (code "67") (name "unconnected-(U1-IN4+-Pad1)") (class "Default")
      (node (ref "U1") (pin "1") (pinfunction "IN4+_1") (pintype "input"))
    )
    (net (code "68") (name "unconnected-(U1-IN4--Pad56)") (class "Default")
      (node (ref "U1") (pin "56") (pinfunction "IN4-_56") (pintype "input"))
    )
    (net (code "69") (name "unconnected-(U1-IN5+-Pad55)") (class "Default")
      (node (ref "U1") (pin "55") (pinfunction "IN5+_55") (pintype "input"))
    )
    (net (code "70") (name "unconnected-(U1-IN5--Pad54)") (class "Default")
      (node (ref "U1") (pin "54") (pinfunction "IN5-_54") (pintype "input"))
    )
    (net (code "71") (name "unconnected-(U1-IN10+-Pad45)") (class "Default")
      (node (ref "U1") (pin "45") (pinfunction "IN10+_45") (pintype "input"))
    )
    (net (code "72") (name "unconnected-(U1-IN10--Pad44)") (class "Default")
      (node (ref "U1") (pin "44") (pinfunction "IN10-_44") (pintype "input"))
    )
    (net (code "73") (name "unconnected-(U1-IN11+-Pad43)") (class "Default")
      (node (ref "U1") (pin "43") (pinfunction "IN11+_43") (pintype "input"))
    )
    (net (code "74") (name "unconnected-(U1-IN11--Pad42)") (class "Default")
      (node (ref "U1") (pin "42") (pinfunction "IN11-_42") (pintype "input"))
    )
    (net (code "75") (name "unconnected-(U1-IN14+-Pad37)") (class "Default")
      (node (ref "U1") (pin "37") (pinfunction "IN14+_37") (pintype "input"))
    )
    (net (code "76") (name "unconnected-(U1-IN14--Pad36)") (class "Default")
      (node (ref "U1") (pin "36") (pinfunction "IN14-_36") (pintype "input"))
    )
    (net (code "77") (name "unconnected-(U1-IN15+-Pad35)") (class "Default")
      (node (ref "U1") (pin "35") (pinfunction "IN15+_35") (pintype "input"))
    )
    (net (code "78") (name "unconnected-(U1-IN15--Pad34)") (class "Default")
      (node (ref "U1") (pin "34") (pinfunction "IN15-_34") (pintype "input"))
    )
    (net (code "79") (name "unconnected-(U1-MISO--Pad24)") (class "Default")
      (node (ref "U1") (pin "24") (pinfunction "MISO-_24") (pintype "output"))
    )
    (net (code "80") (name "unconnected-(U1-MOSI--Pad22)") (class "Default")
      (node (ref "U1") (pin "22") (pinfunction "MOSI-_22") (pintype "input"))
    )
    (net (code "81") (name "unconnected-(U1-SCLK--Pad20)") (class "Default")
      (node (ref "U1") (pin "20") (pinfunction "SCLK-_20") (pintype "input"))
    )
    (net (code "82") (name "unconnected-(U1-~{CS}--Pad18)") (class "Default")
      (node (ref "U1") (pin "18") (pinfunction "~{CS}-_18") (pintype "input"))
    )
    (net (code "83") (name "unconnected-(U3-PA02-Pad3)") (class "Default")
      (node (ref "U3") (pin "3") (pinfunction "PA02_3") (pintype "bidirectional"))
    )
    (net (code "84") (name "unconnected-(U3-PA03-Pad4)") (class "Default")
      (node (ref "U3") (pin "4") (pinfunction "PA03_4") (pintype "bidirectional"))
    )
    (net (code "85") (name "unconnected-(U3-PA04-Pad13)") (class "Default")
      (node (ref "U3") (pin "13") (pinfunction "PA04_13") (pintype "bidirectional"))
    )
    (net (code "86") (name "unconnected-(U3-PA05-Pad14)") (class "Default")
      (node (ref "U3") (pin "14") (pinfunction "PA05_14") (pintype "bidirectional"))
    )
    (net (code "87") (name "unconnected-(U3-PA06-Pad15)") (class "Default")
      (node (ref "U3") (pin "15") (pinfunction "PA06_15") (pintype "bidirectional"))
    )
    (net (code "88") (name "unconnected-(U3-PA13-Pad30)") (class "Default")
      (node (ref "U3") (pin "30") (pinfunction "PA13_30") (pintype "bidirectional"))
    )
    (net (code "89") (name "unconnected-(U3-PA14-Pad31)") (class "Default")
      (node (ref "U3") (pin "31") (pinfunction "PA14_31") (pintype "bidirectional"))
    )
    (net (code "90") (name "unconnected-(U3-PA15-Pad32)") (class "Default")
      (node (ref "U3") (pin "32") (pinfunction "PA15_32") (pintype "bidirectional"))
    )
    (net (code "91") (name "unconnected-(U3-PA20-Pad41)") (class "Default")
      (node (ref "U3") (pin "41") (pinfunction "PA20_41") (pintype "bidirectional"))
    )
    (net (code "92") (name "unconnected-(U3-PA22-Pad43)") (class "Default")
      (node (ref "U3") (pin "43") (pinfunction "PA22_43") (pintype "bidirectional"))
    )
    (net (code "93") (name "unconnected-(U3-PA23-Pad44)") (class "Default")
      (node (ref "U3") (pin "44") (pinfunction "PA23_44") (pintype "bidirectional"))
    )
    (net (code "94") (name "unconnected-(U3-PA24-Pad45)") (class "Default")
      (node (ref "U3") (pin "45") (pinfunction "PA24_45") (pintype "bidirectional"))
    )
    (net (code "95") (name "unconnected-(U3-PA25-Pad46)") (class "Default")
      (node (ref "U3") (pin "46") (pinfunction "PA25_46") (pintype "bidirectional"))
    )
    (net (code "96") (name "unconnected-(U3-PA27-Pad51)") (class "Default")
      (node (ref "U3") (pin "51") (pinfunction "PA27_51") (pintype "bidirectional"))
    )
    (net (code "97") (name "unconnected-(U3-PB00-Pad61)") (class "Default")
      (node (ref "U3") (pin "61") (pinfunction "PB00_61") (pintype "bidirectional"))
    )
    (net (code "98") (name "unconnected-(U3-PB01-Pad62)") (class "Default")
      (node (ref "U3") (pin "62") (pinfunction "PB01_62") (pintype "bidirectional"))
    )
    (net (code "99") (name "unconnected-(U3-PB02-Pad63)") (class "Default")
      (node (ref "U3") (pin "63") (pinfunction "PB02_63") (pintype "bidirectional"))
    )
    (net (code "100") (name "unconnected-(U3-PB03-Pad64)") (class "Default")
      (node (ref "U3") (pin "64") (pinfunction "PB03_64") (pintype "bidirectional"))
    )
    (net (code "101") (name "unconnected-(U3-PB04-Pad5)") (class "Default")
      (node (ref "U3") (pin "5") (pinfunction "PB04_5") (pintype "bidirectional"))
    )
    (net (code "102") (name "unconnected-(U3-PB05-Pad6)") (class "Default")
      (node (ref "U3") (pin "6") (pinfunction "PB05_6") (pintype "bidirectional"))
    )
    (net (code "103") (name "unconnected-(U3-PB06-Pad9)") (class "Default")
      (node (ref "U3") (pin "9") (pinfunction "PB06_9") (pintype "bidirectional"))
    )
    (net (code "104") (name "unconnected-(U3-PB07-Pad10)") (class "Default")
      (node (ref "U3") (pin "10") (pinfunction "PB07_10") (pintype "bidirectional"))
    )
    (net (code "105") (name "unconnected-(U3-PB08-Pad11)") (class "Default")
      (node (ref "U3") (pin "11") (pinfunction "PB08_11") (pintype "bidirectional"))
    )
    (net (code "106") (name "unconnected-(U3-PB09-Pad12)") (class "Default")
      (node (ref "U3") (pin "12") (pinfunction "PB09_12") (pintype "bidirectional"))
    )
    (net (code "107") (name "unconnected-(U3-PB10-Pad23)") (class "Default")
      (node (ref "U3") (pin "23") (pinfunction "PB10_23") (pintype "bidirectional"))
    )
    (net (code "108") (name "unconnected-(U3-PB12-Pad25)") (class "Default")
      (node (ref "U3") (pin "25") (pinfunction "PB12_25") (pintype "bidirectional"))
    )
    (net (code "109") (name "unconnected-(U3-PB13-Pad26)") (class "Default")
      (node (ref "U3") (pin "26") (pinfunction "PB13_26") (pintype "bidirectional"))
    )
    (net (code "110") (name "unconnected-(U3-PB14-Pad27)") (class "Default")
      (node (ref "U3") (pin "27") (pinfunction "PB14_27") (pintype "bidirectional"))
    )
    (net (code "111") (name "unconnected-(U3-PB15-Pad28)") (class "Default")
      (node (ref "U3") (pin "28") (pinfunction "PB15_28") (pintype "bidirectional"))
    )
    (net (code "112") (name "unconnected-(U3-PB16-Pad39)") (class "Default")
      (node (ref "U3") (pin "39") (pinfunction "PB16_39") (pintype "bidirectional"))
    )
    (net (code "113") (name "unconnected-(U3-PB17-Pad40)") (class "Default")
      (node (ref "U3") (pin "40") (pinfunction "PB17_40") (pintype "bidirectional"))
    )
    (net (code "114") (name "unconnected-(U3-PB22-Pad49)") (class "Default")
      (node (ref "U3") (pin "49") (pinfunction "PB22_49") (pintype "bidirectional"))
    )
    (net (code "115") (name "unconnected-(U3-PB23-Pad50)") (class "Default")
      (node (ref "U3") (pin "50") (pinfunction "PB23_50") (pintype "bidirectional"))
    )
    (net (code "116") (name "unconnected-(U3-PB30-Pad59)") (class "Default")
      (node (ref "U3") (pin "59") (pinfunction "PB30_59") (pintype "bidirectional"))
    )
    (net (code "117") (name "unconnected-(U3-PB31-Pad60)") (class "Default")
      (node (ref "U3") (pin "60") (pinfunction "PB31_60") (pintype "bidirectional"))
    )
  )
)
